# PocketPowerSource4_3.net
KiCad netlist of a schematic drawn in EAGLE
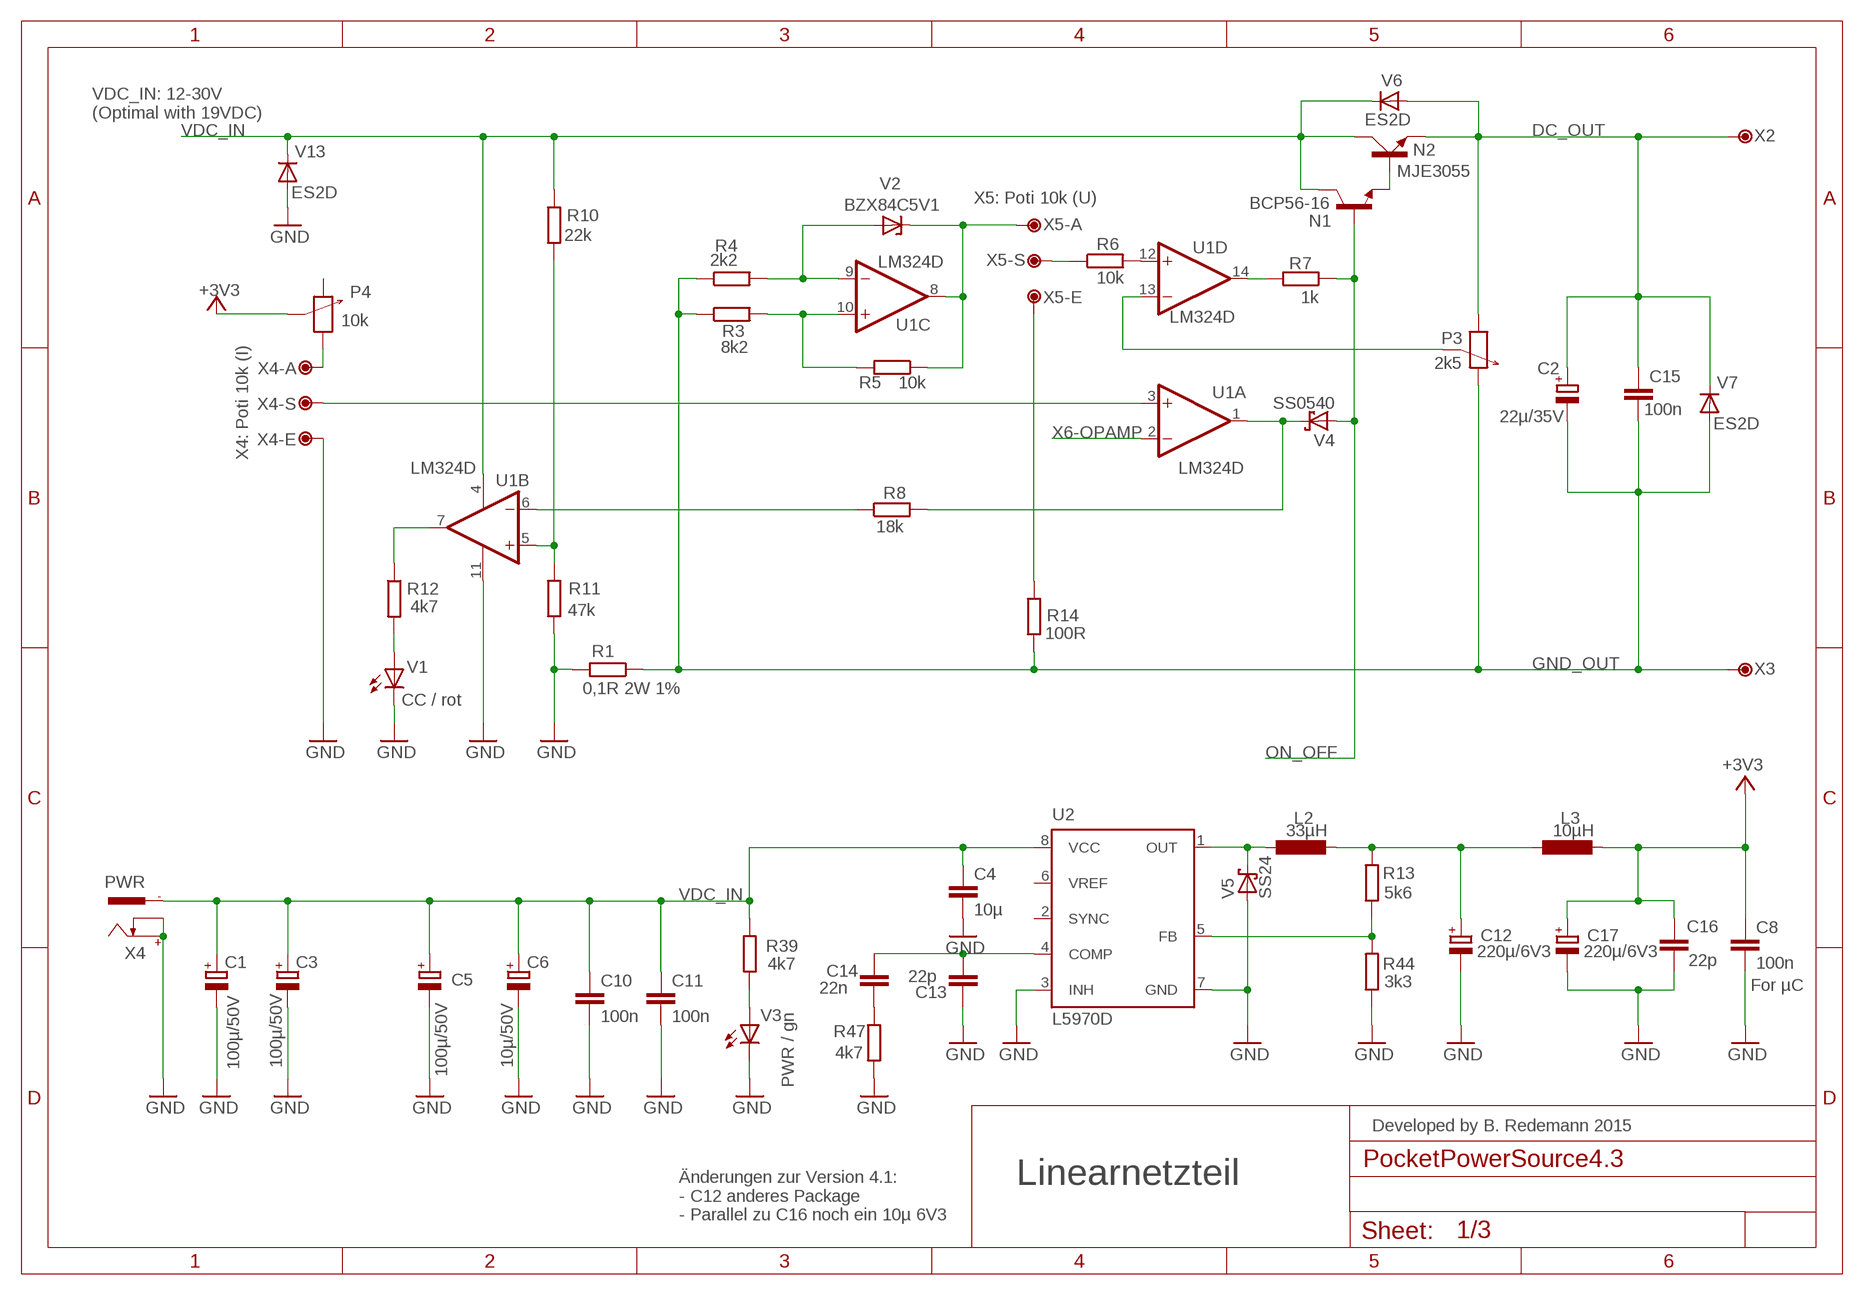
[diagram p0: schematic, sheet 1]
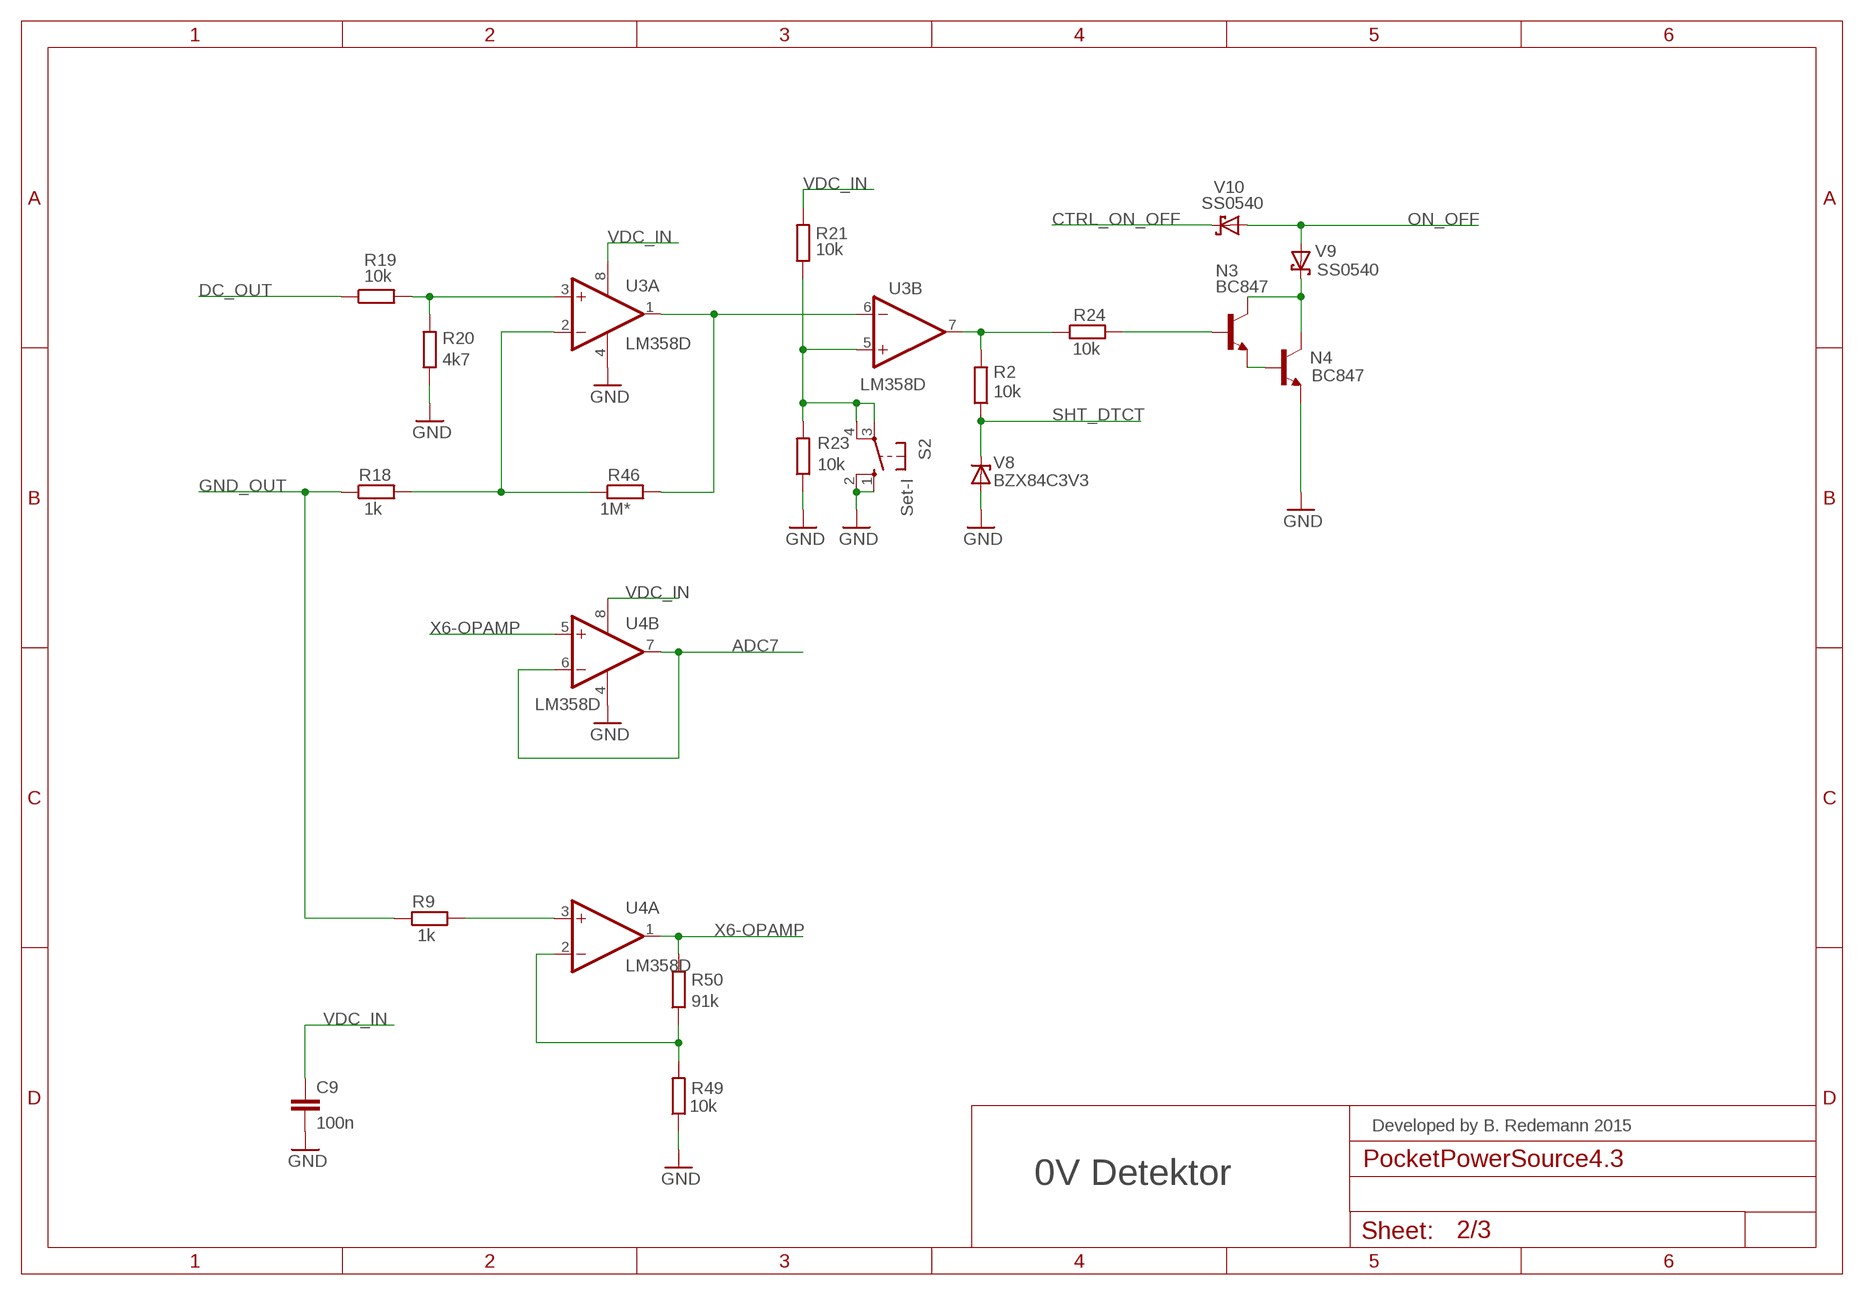
[diagram p1: schematic, sheet 2]
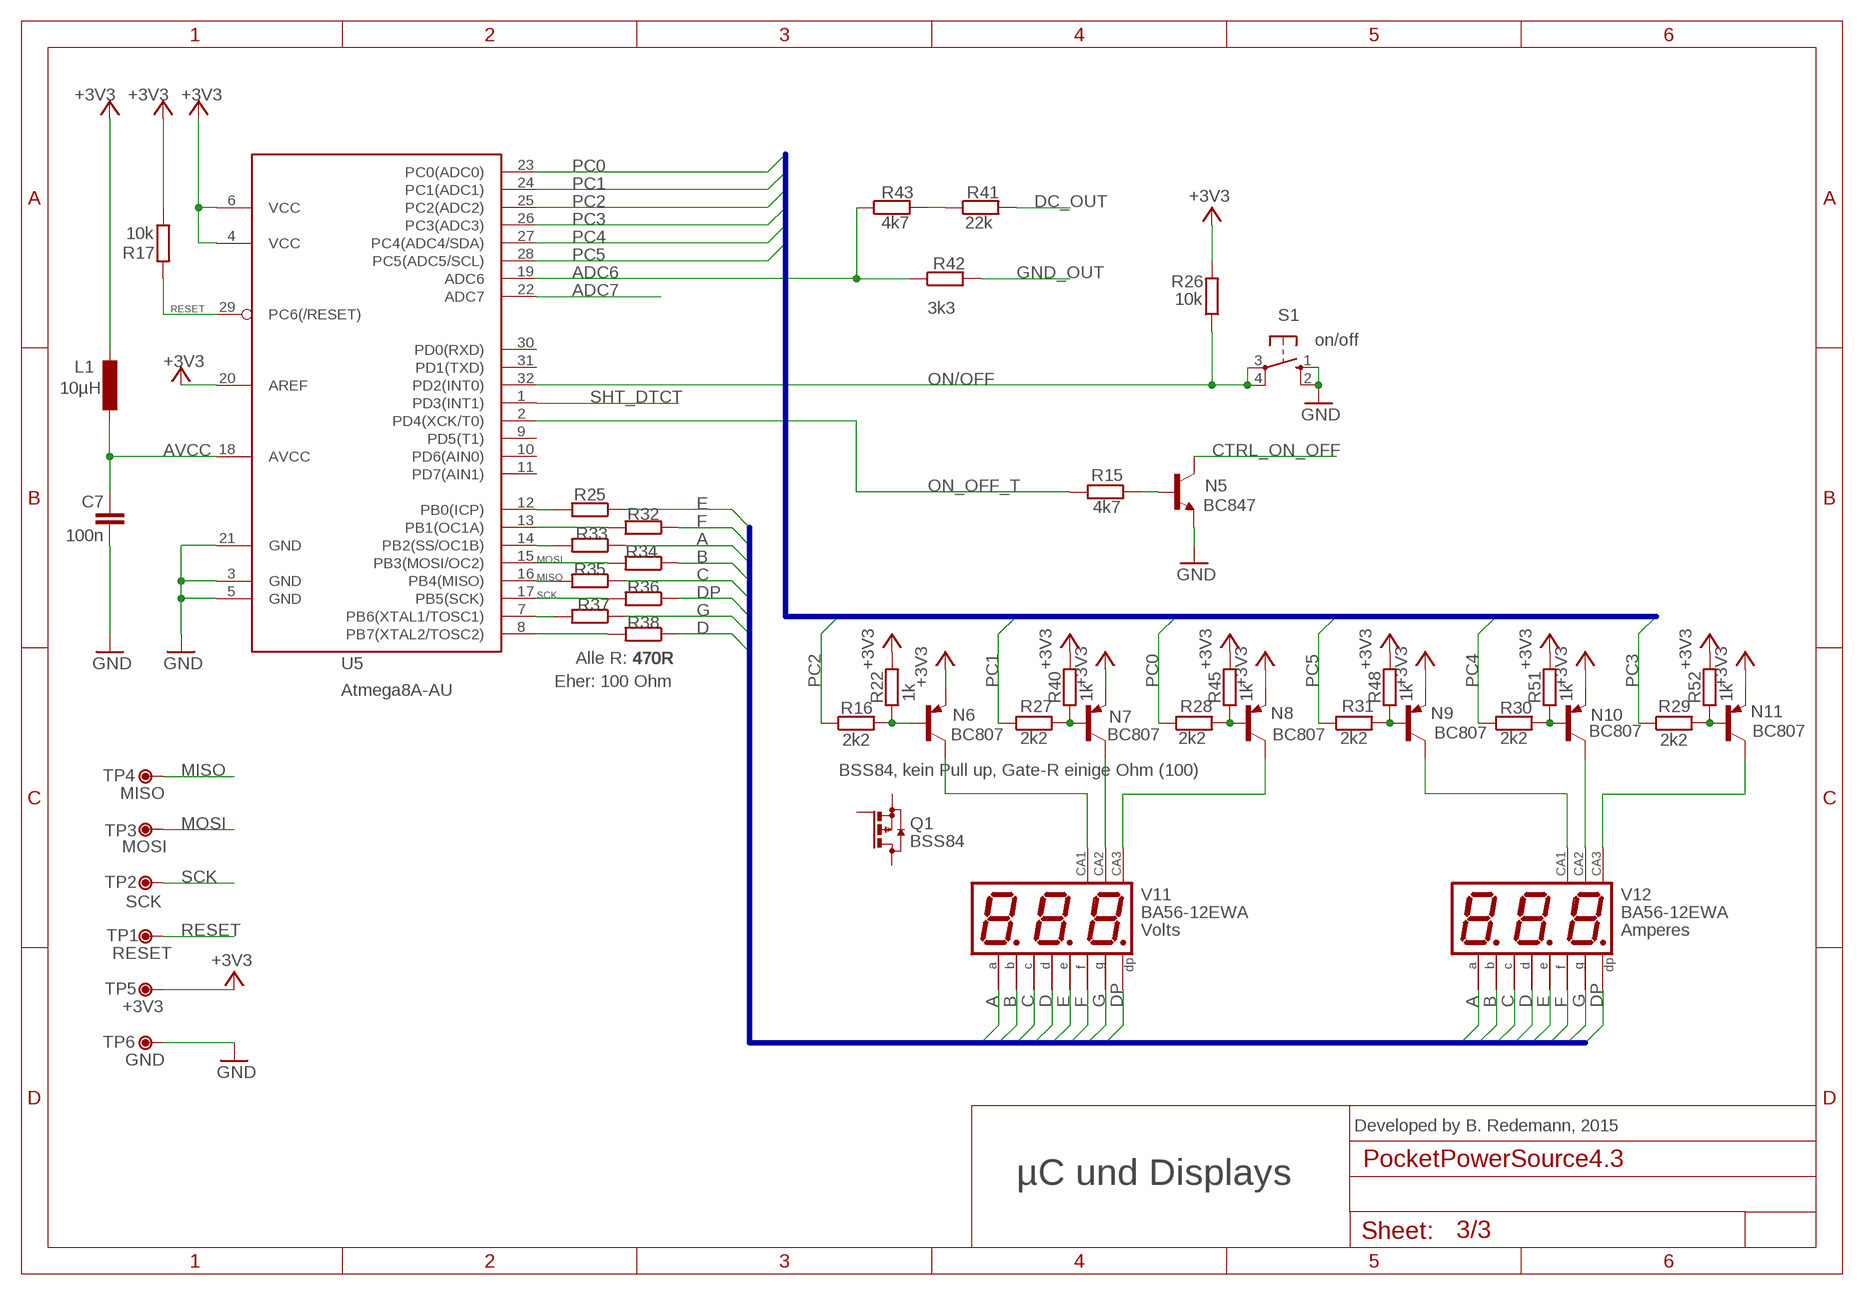
[diagram p2: schematic, sheet 3]

(export (version "E")
  (design (tool "Eeschema 10.0.6"))
  (components
    (comp (ref "C1")
      (value "100µ/50V")
      (footprint "eagle-import:PANASONIC_F")
      (libsource (lib "eagle-import") (part "CPOL-EUF"))
    )
    (comp (ref "C2")
      (value "22µ/35V")
      (footprint "eagle-import:PANASONIC_C")
      (libsource (lib "eagle-import") (part "CPOL-EUC"))
    )
    (comp (ref "C3")
      (value "100µ/50V")
      (footprint "eagle-import:PANASONIC_F")
      (libsource (lib "eagle-import") (part "CPOL-EUF"))
    )
    (comp (ref "C4")
      (value "10µ")
      (footprint "eagle-import:C1210")
      (libsource (lib "eagle-import") (part "C-EUC1210"))
    )
    (comp (ref "C5")
      (value "100µ/50V")
      (footprint "eagle-import:PANASONIC_F")
      (libsource (lib "eagle-import") (part "CPOL-EUF"))
    )
    (comp (ref "C6")
      (value "10µ/50V")
      (footprint "eagle-import:PANASONIC_D")
      (libsource (lib "eagle-import") (part "CPOL-EUD"))
    )
    (comp (ref "C8")
      (value "100n")
      (footprint "eagle-import:C0603K")
      (libsource (lib "eagle-import") (part "C-EUC0603K"))
    )
    (comp (ref "C10")
      (value "100n")
      (footprint "eagle-import:C0603K")
      (libsource (lib "eagle-import") (part "C-EUC0603K"))
    )
    (comp (ref "C11")
      (value "100n")
      (footprint "eagle-import:C0603K")
      (libsource (lib "eagle-import") (part "C-EUC0603K"))
    )
    (comp (ref "C12")
      (value "220µ/6V3")
      (footprint "eagle-import:PANASONIC_D")
      (libsource (lib "eagle-import") (part "CPOL-EUD"))
    )
    (comp (ref "C13")
      (value "22p")
      (footprint "eagle-import:C0805")
      (libsource (lib "eagle-import") (part "C-EUC0805"))
    )
    (comp (ref "C14")
      (value "22n")
      (footprint "eagle-import:C1206")
      (libsource (lib "eagle-import") (part "C-EUC1206"))
    )
    (comp (ref "C15")
      (value "100n")
      (footprint "eagle-import:C0603K")
      (libsource (lib "eagle-import") (part "C-EUC0603K"))
    )
    (comp (ref "C16")
      (value "22p")
      (footprint "eagle-import:C0805")
      (libsource (lib "eagle-import") (part "C-EUC0805"))
    )
    (comp (ref "C17")
      (value "220µ/6V3")
      (footprint "eagle-import:PANASONIC_D")
      (libsource (lib "eagle-import") (part "CPOL-EUD"))
    )
    (comp (ref "L2")
      (value "33µH")
      (footprint "eagle-import:POWER-CHOKE_WE-TPC")
      (libsource (lib "eagle-import") (part "L-EUWE-TPC"))
    )
    (comp (ref "L3")
      (value "10µH")
      (footprint "eagle-import:L4540")
      (libsource (lib "eagle-import") (part "L-EUL4540"))
    )
    (comp (ref "N1")
      (value "BCP56-16")
      (footprint "eagle-import:PG-SOT-223")
      (libsource (lib "eagle-import") (part "BCP56"))
    )
    (comp (ref "N2")
      (value "MJE3055")
      (footprint "eagle-import:TO220AV")
      (libsource (lib "eagle-import") (part "MJE3055"))
    )
    (comp (ref "P3")
      (value "2k5")
      (footprint "eagle-import:PT6")
      (libsource (lib "eagle-import") (part "PT6"))
    )
    (comp (ref "P4")
      (value "10k")
      (footprint "eagle-import:PT6")
      (libsource (lib "eagle-import") (part "PT6"))
    )
    (comp (ref "R1")
      (value "0,1R 2W 1%")
      (footprint "eagle-import:R2512")
      (libsource (lib "eagle-import") (part "R-EU_R2512"))
    )
    (comp (ref "R3")
      (value "8k2")
      (footprint "eagle-import:R0603")
      (libsource (lib "eagle-import") (part "R-EU_R0603"))
    )
    (comp (ref "R4")
      (value "2k2")
      (footprint "eagle-import:R0805")
      (libsource (lib "eagle-import") (part "R-EU_R0805"))
    )
    (comp (ref "R5")
      (value "10k")
      (footprint "eagle-import:R0603")
      (libsource (lib "eagle-import") (part "R-EU_R0603"))
    )
    (comp (ref "R6")
      (value "10k")
      (footprint "eagle-import:R0603")
      (libsource (lib "eagle-import") (part "R-EU_R0603"))
    )
    (comp (ref "R7")
      (value "1k")
      (footprint "eagle-import:R0603")
      (libsource (lib "eagle-import") (part "R-EU_R0603"))
    )
    (comp (ref "R8")
      (value "18k")
      (footprint "eagle-import:R1206")
      (libsource (lib "eagle-import") (part "R-EU_R1206"))
    )
    (comp (ref "R10")
      (value "22k")
      (footprint "eagle-import:R0603")
      (libsource (lib "eagle-import") (part "R-EU_R0603"))
    )
    (comp (ref "R11")
      (value "47k")
      (footprint "eagle-import:R0603")
      (libsource (lib "eagle-import") (part "R-EU_R0603"))
    )
    (comp (ref "R12")
      (value "4k7")
      (footprint "eagle-import:R1206")
      (libsource (lib "eagle-import") (part "R-EU_R1206"))
    )
    (comp (ref "R13")
      (value "5k6")
      (footprint "eagle-import:R0603")
      (libsource (lib "eagle-import") (part "R-EU_R0603"))
    )
    (comp (ref "R14")
      (value "100R")
      (footprint "eagle-import:R0603")
      (libsource (lib "eagle-import") (part "R-EU_R0603"))
    )
    (comp (ref "R39")
      (value "4k7")
      (footprint "eagle-import:R1206")
      (libsource (lib "eagle-import") (part "R-EU_R1206"))
    )
    (comp (ref "R44")
      (value "3k3")
      (footprint "eagle-import:R0603")
      (libsource (lib "eagle-import") (part "R-EU_R0603"))
    )
    (comp (ref "R47")
      (value "4k7")
      (footprint "eagle-import:R1206")
      (libsource (lib "eagle-import") (part "R-EU_R1206"))
    )
    (comp (ref "U1")
      (value "LM324D")
      (footprint "eagle-import:SO14")
      (fields (field (name "MF") "STMicroelectronics"))
      (libsource (lib "eagle-import") (part "LM324D"))
    )
    (comp (ref "U2")
      (value "L5970D")
      (footprint "eagle-import:SO08")
      (fields (field (name "MF") "STMicroelectronics"))
      (libsource (lib "eagle-import") (part "L5970D"))
    )
    (comp (ref "V1")
      (value "CC / rot")
      (footprint "eagle-import:LED3MM")
      (libsource (lib "eagle-import") (part "LED3MM"))
    )
    (comp (ref "V2")
      (value "BZX84C5V1")
      (footprint "eagle-import:TO236")
      (libsource (lib "eagle-import") (part "BZX84CSMD"))
    )
    (comp (ref "V3")
      (value "PWR / gn")
      (footprint "eagle-import:LED3MM")
      (libsource (lib "eagle-import") (part "LED3MM"))
    )
    (comp (ref "V4")
      (value "SS0540")
      (footprint "eagle-import:SOD123")
      (libsource (lib "eagle-import") (part "SS0540"))
    )
    (comp (ref "V5")
      (value "SS24")
      (footprint "eagle-import:SMB")
      (libsource (lib "eagle-import") (part "MBRS130LT3"))
    )
    (comp (ref "V6")
      (value "ES2D")
      (footprint "eagle-import:SMB")
      (libsource (lib "eagle-import") (part "ES2D"))
    )
    (comp (ref "V7")
      (value "ES2D")
      (footprint "eagle-import:SMB")
      (libsource (lib "eagle-import") (part "ES2D"))
    )
    (comp (ref "V13")
      (value "ES2D")
      (footprint "eagle-import:SMB")
      (libsource (lib "eagle-import") (part "ES2D"))
    )
    (comp (ref "X2")
      (value "DC_OUT")
      (footprint "eagle-import:P1-13")
      (libsource (lib "eagle-import") (part "TPPAD1-13"))
    )
    (comp (ref "X3")
      (value "GND_OUT")
      (footprint "eagle-import:P1-13")
      (libsource (lib "eagle-import") (part "TPPAD1-13"))
    )
    (comp (ref "X4")
      (value "PWR")
      (footprint "eagle-import:737992-5")
      (libsource (lib "eagle-import") (part "737992-55"))
    )
    (comp (ref "X4-A")
      (value "P_I-A")
      (footprint "eagle-import:P1-13")
      (libsource (lib "eagle-import") (part "TPPAD1-13"))
    )
    (comp (ref "X4-E")
      (value "P_I-E")
      (footprint "eagle-import:P1-13")
      (libsource (lib "eagle-import") (part "TPPAD1-13"))
    )
    (comp (ref "X4-S")
      (value "P_I-W")
      (footprint "eagle-import:P1-13")
      (libsource (lib "eagle-import") (part "TPPAD1-13"))
    )
    (comp (ref "X5-A")
      (value "P_U-A")
      (footprint "eagle-import:P1-13")
      (libsource (lib "eagle-import") (part "TPPAD1-13"))
    )
    (comp (ref "X5-E")
      (value "P_U-E")
      (footprint "eagle-import:P1-13")
      (libsource (lib "eagle-import") (part "TPPAD1-13"))
    )
    (comp (ref "X5-S")
      (value "P_U-S")
      (footprint "eagle-import:P1-13")
      (libsource (lib "eagle-import") (part "TPPAD1-13"))
    )
    (comp (ref "C9")
      (value "100n")
      (footprint "eagle-import:C0603K")
      (libsource (lib "eagle-import") (part "C-EUC0603K"))
    )
    (comp (ref "N3")
      (value "BC847")
      (footprint "eagle-import:SOT23")
      (libsource (lib "eagle-import") (part "BC847"))
    )
    (comp (ref "N4")
      (value "BC847")
      (footprint "eagle-import:SOT23")
      (libsource (lib "eagle-import") (part "BC847"))
    )
    (comp (ref "R2")
      (value "10k")
      (footprint "eagle-import:R0603")
      (libsource (lib "eagle-import") (part "R-EU_R0603"))
    )
    (comp (ref "R9")
      (value "1k")
      (footprint "eagle-import:R0603")
      (libsource (lib "eagle-import") (part "R-EU_R0603"))
    )
    (comp (ref "R18")
      (value "1k")
      (footprint "eagle-import:R0603")
      (libsource (lib "eagle-import") (part "R-EU_R0603"))
    )
    (comp (ref "R19")
      (value "10k")
      (footprint "eagle-import:R0603")
      (libsource (lib "eagle-import") (part "R-EU_R0603"))
    )
    (comp (ref "R20")
      (value "4k7")
      (footprint "eagle-import:R1206")
      (libsource (lib "eagle-import") (part "R-EU_R1206"))
    )
    (comp (ref "R21")
      (value "10k")
      (footprint "eagle-import:R0603")
      (libsource (lib "eagle-import") (part "R-EU_R0603"))
    )
    (comp (ref "R23")
      (value "10k")
      (footprint "eagle-import:R0603")
      (libsource (lib "eagle-import") (part "R-EU_R0603"))
    )
    (comp (ref "R24")
      (value "10k")
      (footprint "eagle-import:R0603")
      (libsource (lib "eagle-import") (part "R-EU_R0603"))
    )
    (comp (ref "R46")
      (value "1M*")
      (footprint "eagle-import:R0603")
      (libsource (lib "eagle-import") (part "R-EU_R0603"))
    )
    (comp (ref "R49")
      (value "10k")
      (footprint "eagle-import:R0603")
      (libsource (lib "eagle-import") (part "R-EU_R0603"))
    )
    (comp (ref "R50")
      (value "91k")
      (footprint "eagle-import:R0805")
      (libsource (lib "eagle-import") (part "R-EU_R0805"))
    )
    (comp (ref "S2")
      (value "Set-I")
      (footprint "eagle-import:B3F-10XX")
      (fields (field (name "MPN") "B3F-1000"))
      (libsource (lib "eagle-import") (part "10-XX"))
    )
    (comp (ref "U3")
      (value "LM358D")
      (footprint "eagle-import:SO08")
      (fields (field (name "MF") "STMicroelectronics"))
      (libsource (lib "eagle-import") (part "LM358D"))
    )
    (comp (ref "U4")
      (value "LM358D")
      (footprint "eagle-import:SO08")
      (fields (field (name "MF") "STMicroelectronics"))
      (libsource (lib "eagle-import") (part "LM358D"))
    )
    (comp (ref "V8")
      (value "BZX84C3V3")
      (footprint "eagle-import:TO236")
      (libsource (lib "eagle-import") (part "BZX84CSMD"))
    )
    (comp (ref "V9")
      (value "SS0540")
      (footprint "eagle-import:SOD123")
      (libsource (lib "eagle-import") (part "SS0540"))
    )
    (comp (ref "V10")
      (value "SS0540")
      (footprint "eagle-import:SOD123")
      (libsource (lib "eagle-import") (part "SS0540"))
    )
    (comp (ref "C7")
      (value "100n")
      (footprint "eagle-import:C0603K")
      (libsource (lib "eagle-import") (part "C-EUC0603K"))
    )
    (comp (ref "L1")
      (value "10µH")
      (footprint "eagle-import:L2825P")
      (libsource (lib "eagle-import") (part "resistor_L-EUL2825P"))
    )
    (comp (ref "N5")
      (value "BC847")
      (footprint "eagle-import:SOT23")
      (libsource (lib "eagle-import") (part "BC847"))
    )
    (comp (ref "N6")
      (value "BC807")
      (footprint "eagle-import:SOT23-BEC")
      (libsource (lib "eagle-import") (part "-PNP-SOT23-BECBC807-16"))
    )
    (comp (ref "N7")
      (value "BC807")
      (footprint "eagle-import:SOT23-BEC")
      (libsource (lib "eagle-import") (part "-PNP-SOT23-BECBC807-16"))
    )
    (comp (ref "N8")
      (value "BC807")
      (footprint "eagle-import:SOT23-BEC")
      (libsource (lib "eagle-import") (part "-PNP-SOT23-BECBC807-16"))
    )
    (comp (ref "N9")
      (value "BC807")
      (footprint "eagle-import:SOT23-BEC")
      (libsource (lib "eagle-import") (part "-PNP-SOT23-BECBC807-16"))
    )
    (comp (ref "N10")
      (value "BC807")
      (footprint "eagle-import:SOT23-BEC")
      (libsource (lib "eagle-import") (part "-PNP-SOT23-BECBC807-16"))
    )
    (comp (ref "N11")
      (value "BC807")
      (footprint "eagle-import:SOT23-BEC")
      (libsource (lib "eagle-import") (part "-PNP-SOT23-BECBC807-16"))
    )
    (comp (ref "Q1")
      (value "BSS84")
      (footprint "eagle-import:SOT23")
      (libsource (lib "eagle-import") (part "BSS84"))
    )
    (comp (ref "R15")
      (value "4k7")
      (footprint "eagle-import:R1206")
      (libsource (lib "eagle-import") (part "R-EU_R1206"))
    )
    (comp (ref "R16")
      (value "2k2")
      (footprint "eagle-import:R1206")
      (libsource (lib "eagle-import") (part "R-EU_R1206"))
    )
    (comp (ref "R17")
      (value "10k")
      (footprint "eagle-import:R0603")
      (libsource (lib "eagle-import") (part "R-EU_R0603"))
    )
    (comp (ref "R22")
      (value "1k")
      (footprint "eagle-import:R0603")
      (libsource (lib "eagle-import") (part "R-EU_R0603"))
    )
    (comp (ref "R25")
      (value "470R")
      (footprint "eagle-import:R0805")
      (libsource (lib "eagle-import") (part "R-EU_R0805"))
    )
    (comp (ref "R26")
      (value "10k")
      (footprint "eagle-import:R0603")
      (libsource (lib "eagle-import") (part "R-EU_R0603"))
    )
    (comp (ref "R27")
      (value "2k2")
      (footprint "eagle-import:R1206")
      (libsource (lib "eagle-import") (part "R-EU_R1206"))
    )
    (comp (ref "R28")
      (value "2k2")
      (footprint "eagle-import:R1206")
      (libsource (lib "eagle-import") (part "R-EU_R1206"))
    )
    (comp (ref "R29")
      (value "2k2")
      (footprint "eagle-import:R1206")
      (libsource (lib "eagle-import") (part "R-EU_R1206"))
    )
    (comp (ref "R30")
      (value "2k2")
      (footprint "eagle-import:R1206")
      (libsource (lib "eagle-import") (part "R-EU_R1206"))
    )
    (comp (ref "R31")
      (value "2k2")
      (footprint "eagle-import:R1206")
      (libsource (lib "eagle-import") (part "R-EU_R1206"))
    )
    (comp (ref "R32")
      (value "470R")
      (footprint "eagle-import:R0805")
      (libsource (lib "eagle-import") (part "R-EU_R0805"))
    )
    (comp (ref "R33")
      (value "470R")
      (footprint "eagle-import:R0805")
      (libsource (lib "eagle-import") (part "R-EU_R0805"))
    )
    (comp (ref "R34")
      (value "470R")
      (footprint "eagle-import:R0805")
      (libsource (lib "eagle-import") (part "R-EU_R0805"))
    )
    (comp (ref "R35")
      (value "470R")
      (footprint "eagle-import:R0805")
      (libsource (lib "eagle-import") (part "R-EU_R0805"))
    )
    (comp (ref "R36")
      (value "470R")
      (footprint "eagle-import:R0805")
      (libsource (lib "eagle-import") (part "R-EU_R0805"))
    )
    (comp (ref "R37")
      (value "470R")
      (footprint "eagle-import:R0805")
      (libsource (lib "eagle-import") (part "R-EU_R0805"))
    )
    (comp (ref "R38")
      (value "470R")
      (footprint "eagle-import:R0805")
      (libsource (lib "eagle-import") (part "R-EU_R0805"))
    )
    (comp (ref "R40")
      (value "1k")
      (footprint "eagle-import:R0603")
      (libsource (lib "eagle-import") (part "R-EU_R0603"))
    )
    (comp (ref "R41")
      (value "22k")
      (footprint "eagle-import:R0603")
      (libsource (lib "eagle-import") (part "R-EU_R0603"))
    )
    (comp (ref "R42")
      (value "3k3")
      (footprint "eagle-import:R0603")
      (libsource (lib "eagle-import") (part "R-EU_R0603"))
    )
    (comp (ref "R43")
      (value "4k7")
      (footprint "eagle-import:R1206")
      (libsource (lib "eagle-import") (part "R-EU_R1206"))
    )
    (comp (ref "R45")
      (value "1k")
      (footprint "eagle-import:R0603")
      (libsource (lib "eagle-import") (part "R-EU_R0603"))
    )
    (comp (ref "R48")
      (value "1k")
      (footprint "eagle-import:R0603")
      (libsource (lib "eagle-import") (part "R-EU_R0603"))
    )
    (comp (ref "R51")
      (value "1k")
      (footprint "eagle-import:R0603")
      (libsource (lib "eagle-import") (part "R-EU_R0603"))
    )
    (comp (ref "R52")
      (value "1k")
      (footprint "eagle-import:R0603")
      (libsource (lib "eagle-import") (part "R-EU_R0603"))
    )
    (comp (ref "S1")
      (value "on/off")
      (footprint "eagle-import:B3F-10XX")
      (fields (field (name "MPN") "B3F-1000"))
      (libsource (lib "eagle-import") (part "10-XX"))
    )
    (comp (ref "TP1")
      (value "RESET")
      (footprint "eagle-import:P1-13")
      (libsource (lib "eagle-import") (part "TPPAD1-13"))
    )
    (comp (ref "TP2")
      (value "SCK")
      (footprint "eagle-import:P1-13")
      (libsource (lib "eagle-import") (part "TPPAD1-13"))
    )
    (comp (ref "TP3")
      (value "MOSI")
      (footprint "eagle-import:P1-13")
      (libsource (lib "eagle-import") (part "TPPAD1-13"))
    )
    (comp (ref "TP4")
      (value "MISO")
      (footprint "eagle-import:P1-13")
      (libsource (lib "eagle-import") (part "TPPAD1-13"))
    )
    (comp (ref "TP5")
      (value "+3V3")
      (footprint "eagle-import:P1-13")
      (libsource (lib "eagle-import") (part "TPPAD1-13"))
    )
    (comp (ref "TP6")
      (value "GND")
      (footprint "eagle-import:P1-13")
      (libsource (lib "eagle-import") (part "TPPAD1-13"))
    )
    (comp (ref "U5")
      (value "Atmega8A-AU")
      (footprint "eagle-import:TQFP32-08")
      (fields (field (name "MPN") "ATMEGA8-16AU"))
      (libsource (lib "eagle-import") (part "MEGA8-AI"))
    )
    (comp (ref "V11")
      (value "BA56-12EWA")
      (footprint "eagle-import:BX56-12")
      (libsource (lib "eagle-import") (part "B?56-12WAAE"))
    )
    (comp (ref "V12")
      (value "BA56-12EWA")
      (footprint "eagle-import:BX56-12")
      (libsource (lib "eagle-import") (part "B?56-12WAAE"))
    )
  )
  (nets
    (net (code "1") (name "+3V3") (class "Default")
      (node (ref "C16") (pin "2") (pinfunction "2_2") (pintype "passive"))
      (node (ref "C17") (pin "+") (pinfunction "+_+") (pintype "passive"))
      (node (ref "C8") (pin "1") (pinfunction "1_1") (pintype "passive"))
      (node (ref "L1") (pin "1") (pinfunction "1_1") (pintype "passive"))
      (node (ref "L3") (pin "P$2") (pinfunction "2_P$2") (pintype "passive"))
      (node (ref "N10") (pin "E") (pinfunction "E_E") (pintype "passive"))
      (node (ref "N11") (pin "E") (pinfunction "E_E") (pintype "passive"))
      (node (ref "N6") (pin "E") (pinfunction "E_E") (pintype "passive"))
      (node (ref "N7") (pin "E") (pinfunction "E_E") (pintype "passive"))
      (node (ref "N8") (pin "E") (pinfunction "E_E") (pintype "passive"))
      (node (ref "N9") (pin "E") (pinfunction "E_E") (pintype "passive"))
      (node (ref "P4") (pin "WIPER") (pinfunction "1S_WIPER") (pintype "passive"))
      (node (ref "R17") (pin "1") (pinfunction "1_1") (pintype "passive"))
      (node (ref "R22") (pin "2") (pinfunction "2_2") (pintype "passive"))
      (node (ref "R26") (pin "2") (pinfunction "2_2") (pintype "passive"))
      (node (ref "R40") (pin "2") (pinfunction "2_2") (pintype "passive"))
      (node (ref "R45") (pin "2") (pinfunction "2_2") (pintype "passive"))
      (node (ref "R48") (pin "2") (pinfunction "2_2") (pintype "passive"))
      (node (ref "R51") (pin "2") (pinfunction "2_2") (pintype "passive"))
      (node (ref "R52") (pin "2") (pinfunction "2_2") (pintype "passive"))
      (node (ref "TP5") (pin "TP") (pinfunction "TP_TP") (pintype "bidirectional"))
      (node (ref "U5") (pin "20") (pinfunction "AREF_20") (pintype "passive"))
      (node (ref "U5") (pin "4") (pinfunction "VCC_4") (pintype "power_in"))
      (node (ref "U5") (pin "6") (pinfunction "VCC_6") (pintype "power_in"))
    )
    (net (code "2") (name "A") (class "Default")
      (node (ref "R33") (pin "1") (pinfunction "1_1") (pintype "passive"))
      (node (ref "V11") (pin "11") (pinfunction "A_11") (pintype "passive"))
      (node (ref "V12") (pin "11") (pinfunction "A_11") (pintype "passive"))
    )
    (net (code "3") (name "ADC6") (class "Default")
      (node (ref "R42") (pin "1") (pinfunction "1_1") (pintype "passive"))
      (node (ref "R43") (pin "1") (pinfunction "1_1") (pintype "passive"))
      (node (ref "U5") (pin "19") (pinfunction "ADC6_19") (pintype "bidirectional"))
    )
    (net (code "4") (name "ADC7") (class "Default")
      (node (ref "U4") (pin "6") (pinfunction "-IN_6") (pintype "input"))
      (node (ref "U4") (pin "7") (pinfunction "OUT_7") (pintype "output"))
      (node (ref "U5") (pin "22") (pinfunction "ADC7_22") (pintype "bidirectional"))
    )
    (net (code "5") (name "AVCC") (class "Default")
      (node (ref "C7") (pin "1") (pinfunction "1_1") (pintype "passive"))
      (node (ref "L1") (pin "2") (pinfunction "2_2") (pintype "passive"))
      (node (ref "U5") (pin "18") (pinfunction "AVCC_18") (pintype "power_in"))
    )
    (net (code "6") (name "B") (class "Default")
      (node (ref "R34") (pin "1") (pinfunction "1_1") (pintype "passive"))
      (node (ref "V11") (pin "7") (pinfunction "B_7") (pintype "passive"))
      (node (ref "V12") (pin "7") (pinfunction "B_7") (pintype "passive"))
    )
    (net (code "7") (name "C") (class "Default")
      (node (ref "R35") (pin "1") (pinfunction "1_1") (pintype "passive"))
      (node (ref "V11") (pin "4") (pinfunction "C_4") (pintype "passive"))
      (node (ref "V12") (pin "4") (pinfunction "C_4") (pintype "passive"))
    )
    (net (code "8") (name "CTRL_ON_OFF") (class "Default")
      (node (ref "N5") (pin "3") (pinfunction "C_3") (pintype "passive"))
      (node (ref "V10") (pin "C") (pinfunction "C_C") (pintype "passive"))
    )
    (net (code "9") (name "D") (class "Default")
      (node (ref "R38") (pin "1") (pinfunction "1_1") (pintype "passive"))
      (node (ref "V11") (pin "2") (pinfunction "D_2") (pintype "passive"))
      (node (ref "V12") (pin "2") (pinfunction "D_2") (pintype "passive"))
    )
    (net (code "10") (name "DC_OUT") (class "Default")
      (node (ref "C15") (pin "1") (pinfunction "1_1") (pintype "passive"))
      (node (ref "C2") (pin "+") (pinfunction "+_+") (pintype "passive"))
      (node (ref "N2") (pin "E") (pinfunction "E_E") (pintype "passive"))
      (node (ref "P3") (pin "RIGHT") (pinfunction "1E_RIGHT") (pintype "passive"))
      (node (ref "R19") (pin "1") (pinfunction "1_1") (pintype "passive"))
      (node (ref "R41") (pin "2") (pinfunction "2_2") (pintype "passive"))
      (node (ref "V6") (pin "A") (pinfunction "A_A") (pintype "passive"))
      (node (ref "V7") (pin "C") (pinfunction "C_C") (pintype "passive"))
      (node (ref "X2") (pin "TP") (pinfunction "TP_TP") (pintype "bidirectional"))
    )
    (net (code "11") (name "DP") (class "Default")
      (node (ref "R36") (pin "1") (pinfunction "1_1") (pintype "passive"))
      (node (ref "V11") (pin "3") (pinfunction "DP_3") (pintype "passive"))
      (node (ref "V12") (pin "3") (pinfunction "DP_3") (pintype "passive"))
    )
    (net (code "12") (name "E") (class "Default")
      (node (ref "R25") (pin "1") (pinfunction "1_1") (pintype "passive"))
      (node (ref "V11") (pin "1") (pinfunction "E_1") (pintype "passive"))
      (node (ref "V12") (pin "1") (pinfunction "E_1") (pintype "passive"))
    )
    (net (code "13") (name "F") (class "Default")
      (node (ref "R32") (pin "1") (pinfunction "1_1") (pintype "passive"))
      (node (ref "V11") (pin "10") (pinfunction "F_10") (pintype "passive"))
      (node (ref "V12") (pin "10") (pinfunction "F_10") (pintype "passive"))
    )
    (net (code "14") (name "G") (class "Default")
      (node (ref "R37") (pin "1") (pinfunction "1_1") (pintype "passive"))
      (node (ref "V11") (pin "5") (pinfunction "G_5") (pintype "passive"))
      (node (ref "V12") (pin "5") (pinfunction "G_5") (pintype "passive"))
    )
    (net (code "15") (name "GND") (class "Default")
      (node (ref "C1") (pin "-") (pinfunction "-_-") (pintype "passive"))
      (node (ref "C10") (pin "2") (pinfunction "2_2") (pintype "passive"))
      (node (ref "C11") (pin "2") (pinfunction "2_2") (pintype "passive"))
      (node (ref "C12") (pin "-") (pinfunction "-_-") (pintype "passive"))
      (node (ref "C13") (pin "1") (pinfunction "1_1") (pintype "passive"))
      (node (ref "C16") (pin "1") (pinfunction "1_1") (pintype "passive"))
      (node (ref "C17") (pin "-") (pinfunction "-_-") (pintype "passive"))
      (node (ref "C3") (pin "-") (pinfunction "-_-") (pintype "passive"))
      (node (ref "C4") (pin "2") (pinfunction "2_2") (pintype "passive"))
      (node (ref "C5") (pin "-") (pinfunction "-_-") (pintype "passive"))
      (node (ref "C6") (pin "-") (pinfunction "-_-") (pintype "passive"))
      (node (ref "C7") (pin "2") (pinfunction "2_2") (pintype "passive"))
      (node (ref "C8") (pin "2") (pinfunction "2_2") (pintype "passive"))
      (node (ref "C9") (pin "2") (pinfunction "2_2") (pintype "passive"))
      (node (ref "N4") (pin "2") (pinfunction "E_2") (pintype "passive"))
      (node (ref "N5") (pin "2") (pinfunction "E_2") (pintype "passive"))
      (node (ref "R1") (pin "2") (pinfunction "2_2") (pintype "passive"))
      (node (ref "R11") (pin "1") (pinfunction "1_1") (pintype "passive"))
      (node (ref "R20") (pin "1") (pinfunction "1_1") (pintype "passive"))
      (node (ref "R23") (pin "1") (pinfunction "1_1") (pintype "passive"))
      (node (ref "R44") (pin "1") (pinfunction "1_1") (pintype "passive"))
      (node (ref "R47") (pin "1") (pinfunction "1_1") (pintype "passive"))
      (node (ref "R49") (pin "1") (pinfunction "1_1") (pintype "passive"))
      (node (ref "S1") (pin "1") (pinfunction "S_1") (pintype "passive"))
      (node (ref "S1") (pin "2") (pinfunction "S1_2") (pintype "passive"))
      (node (ref "S2") (pin "1") (pinfunction "S_1") (pintype "passive"))
      (node (ref "S2") (pin "2") (pinfunction "S1_2") (pintype "passive"))
      (node (ref "TP6") (pin "TP") (pinfunction "TP_TP") (pintype "bidirectional"))
      (node (ref "U1") (pin "11") (pinfunction "V-_11") (pintype "power_in"))
      (node (ref "U2") (pin "3") (pinfunction "INH_3") (pintype "input"))
      (node (ref "U2") (pin "7") (pinfunction "GND_7") (pintype "power_in"))
      (node (ref "U3") (pin "4") (pinfunction "V-_4") (pintype "power_in"))
      (node (ref "U4") (pin "4") (pinfunction "V-_4") (pintype "power_in"))
      (node (ref "U5") (pin "21") (pinfunction "GND_21") (pintype "power_in"))
      (node (ref "U5") (pin "3") (pinfunction "GND_3") (pintype "power_in"))
      (node (ref "U5") (pin "5") (pinfunction "GND_5") (pintype "power_in"))
      (node (ref "V1") (pin "K") (pinfunction "C_K") (pintype "passive"))
      (node (ref "V13") (pin "A") (pinfunction "A_A") (pintype "passive"))
      (node (ref "V3") (pin "K") (pinfunction "C_K") (pintype "passive"))
      (node (ref "V5") (pin "A") (pinfunction "A_A") (pintype "passive"))
      (node (ref "V8") (pin "A") (pinfunction "A_A") (pintype "passive"))
      (node (ref "X4") (pin "+") (pinfunction "+_+") (pintype "passive"))
      (node (ref "X4") (pin "K") (pinfunction "K_K") (pintype "passive"))
      (node (ref "X4-E") (pin "TP") (pinfunction "TP_TP") (pintype "bidirectional"))
    )
    (net (code "16") (name "GND_OUT") (class "Default")
      (node (ref "C15") (pin "2") (pinfunction "2_2") (pintype "passive"))
      (node (ref "C2") (pin "-") (pinfunction "-_-") (pintype "passive"))
      (node (ref "P3") (pin "LEFT") (pinfunction "1A_LEFT") (pintype "passive"))
      (node (ref "R1") (pin "1") (pinfunction "1_1") (pintype "passive"))
      (node (ref "R14") (pin "2") (pinfunction "2_2") (pintype "passive"))
      (node (ref "R18") (pin "1") (pinfunction "1_1") (pintype "passive"))
      (node (ref "R3") (pin "1") (pinfunction "1_1") (pintype "passive"))
      (node (ref "R4") (pin "1") (pinfunction "1_1") (pintype "passive"))
      (node (ref "R42") (pin "2") (pinfunction "2_2") (pintype "passive"))
      (node (ref "R9") (pin "1") (pinfunction "1_1") (pintype "passive"))
      (node (ref "V7") (pin "A") (pinfunction "A_A") (pintype "passive"))
      (node (ref "X3") (pin "TP") (pinfunction "TP_TP") (pintype "bidirectional"))
    )
    (net (code "17") (name "MISO") (class "Default")
      (node (ref "R35") (pin "2") (pinfunction "2_2") (pintype "passive"))
      (node (ref "TP4") (pin "TP") (pinfunction "TP_TP") (pintype "bidirectional"))
      (node (ref "U5") (pin "16") (pinfunction "PB4(MISO)_16") (pintype "bidirectional"))
    )
    (net (code "18") (name "MOSI") (class "Default")
      (node (ref "R34") (pin "2") (pinfunction "2_2") (pintype "passive"))
      (node (ref "TP3") (pin "TP") (pinfunction "TP_TP") (pintype "bidirectional"))
      (node (ref "U5") (pin "15") (pinfunction "PB3(MOSI/OC2)_15") (pintype "bidirectional"))
    )
    (net (code "19") (name "Net-(C14-Pad2)") (class "Default")
      (node (ref "C14") (pin "2") (pinfunction "2_2") (pintype "passive"))
      (node (ref "R47") (pin "2") (pinfunction "2_2") (pintype "passive"))
    )
    (net (code "20") (name "Net-(L3-1)") (class "Default")
      (node (ref "C12") (pin "+") (pinfunction "+_+") (pintype "passive"))
      (node (ref "L2") (pin "2") (pinfunction "2_2") (pintype "passive"))
      (node (ref "L3") (pin "P$1") (pinfunction "1_P$1") (pintype "passive"))
      (node (ref "R13") (pin "2") (pinfunction "2_2") (pintype "passive"))
    )
    (net (code "21") (name "Net-(N1-E)") (class "Default")
      (node (ref "N1") (pin "3") (pinfunction "E_3") (pintype "passive"))
      (node (ref "N2") (pin "B") (pinfunction "B_B") (pintype "passive"))
    )
    (net (code "22") (name "Net-(N3-B)") (class "Default")
      (node (ref "N3") (pin "1") (pinfunction "B_1") (pintype "passive"))
      (node (ref "R24") (pin "2") (pinfunction "2_2") (pintype "passive"))
    )
    (net (code "23") (name "Net-(N3-C)") (class "Default")
      (node (ref "N3") (pin "3") (pinfunction "C_3") (pintype "passive"))
      (node (ref "N4") (pin "3") (pinfunction "C_3") (pintype "passive"))
      (node (ref "V9") (pin "C") (pinfunction "C_C") (pintype "passive"))
    )
    (net (code "24") (name "Net-(N3-E)") (class "Default")
      (node (ref "N3") (pin "2") (pinfunction "E_2") (pintype "passive"))
      (node (ref "N4") (pin "1") (pinfunction "B_1") (pintype "passive"))
    )
    (net (code "25") (name "Net-(N5-B)") (class "Default")
      (node (ref "N5") (pin "1") (pinfunction "B_1") (pintype "passive"))
      (node (ref "R15") (pin "1") (pinfunction "1_1") (pintype "passive"))
    )
    (net (code "26") (name "Net-(N6-PadB)") (class "Default")
      (node (ref "N6") (pin "B") (pinfunction "B_B") (pintype "passive"))
      (node (ref "R16") (pin "2") (pinfunction "2_2") (pintype "passive"))
      (node (ref "R22") (pin "1") (pinfunction "1_1") (pintype "passive"))
    )
    (net (code "27") (name "Net-(N6-PadC)") (class "Default")
      (node (ref "N6") (pin "C") (pinfunction "C_C") (pintype "passive"))
      (node (ref "V11") (pin "12") (pinfunction "CA_12") (pintype "passive"))
    )
    (net (code "28") (name "Net-(N7-PadB)") (class "Default")
      (node (ref "N7") (pin "B") (pinfunction "B_B") (pintype "passive"))
      (node (ref "R27") (pin "2") (pinfunction "2_2") (pintype "passive"))
      (node (ref "R40") (pin "1") (pinfunction "1_1") (pintype "passive"))
    )
    (net (code "29") (name "Net-(N7-PadC)") (class "Default")
      (node (ref "N7") (pin "C") (pinfunction "C_C") (pintype "passive"))
      (node (ref "V11") (pin "9") (pinfunction "CA_9") (pintype "passive"))
    )
    (net (code "30") (name "Net-(N8-PadB)") (class "Default")
      (node (ref "N8") (pin "B") (pinfunction "B_B") (pintype "passive"))
      (node (ref "R28") (pin "2") (pinfunction "2_2") (pintype "passive"))
      (node (ref "R45") (pin "1") (pinfunction "1_1") (pintype "passive"))
    )
    (net (code "31") (name "Net-(N8-PadC)") (class "Default")
      (node (ref "N8") (pin "C") (pinfunction "C_C") (pintype "passive"))
      (node (ref "V11") (pin "8") (pinfunction "CA_8") (pintype "passive"))
    )
    (net (code "32") (name "Net-(N9-PadB)") (class "Default")
      (node (ref "N9") (pin "B") (pinfunction "B_B") (pintype "passive"))
      (node (ref "R31") (pin "2") (pinfunction "2_2") (pintype "passive"))
      (node (ref "R48") (pin "1") (pinfunction "1_1") (pintype "passive"))
    )
    (net (code "33") (name "Net-(N9-PadC)") (class "Default")
      (node (ref "N9") (pin "C") (pinfunction "C_C") (pintype "passive"))
      (node (ref "V12") (pin "12") (pinfunction "CA_12") (pintype "passive"))
    )
    (net (code "34") (name "Net-(N10-PadB)") (class "Default")
      (node (ref "N10") (pin "B") (pinfunction "B_B") (pintype "passive"))
      (node (ref "R30") (pin "2") (pinfunction "2_2") (pintype "passive"))
      (node (ref "R51") (pin "1") (pinfunction "1_1") (pintype "passive"))
    )
    (net (code "35") (name "Net-(N10-PadC)") (class "Default")
      (node (ref "N10") (pin "C") (pinfunction "C_C") (pintype "passive"))
      (node (ref "V12") (pin "9") (pinfunction "CA_9") (pintype "passive"))
    )
    (net (code "36") (name "Net-(N11-PadB)") (class "Default")
      (node (ref "N11") (pin "B") (pinfunction "B_B") (pintype "passive"))
      (node (ref "R29") (pin "2") (pinfunction "2_2") (pintype "passive"))
      (node (ref "R52") (pin "1") (pinfunction "1_1") (pintype "passive"))
    )
    (net (code "37") (name "Net-(N11-PadC)") (class "Default")
      (node (ref "N11") (pin "C") (pinfunction "C_C") (pintype "passive"))
      (node (ref "V12") (pin "8") (pinfunction "CA_8") (pintype "passive"))
    )
    (net (code "38") (name "Net-(P3-1S)") (class "Default")
      (node (ref "P3") (pin "WIPER") (pinfunction "1S_WIPER") (pintype "passive"))
      (node (ref "U1") (pin "13") (pinfunction "-IN_13") (pintype "input"))
    )
    (net (code "39") (name "Net-(P4-1E)") (class "Default")
      (node (ref "P4") (pin "RIGHT") (pinfunction "1E_RIGHT") (pintype "passive"))
      (node (ref "X4-A") (pin "TP") (pinfunction "TP_TP") (pintype "bidirectional"))
    )
    (net (code "40") (name "Net-(R6-Pad1)") (class "Default")
      (node (ref "R6") (pin "1") (pinfunction "1_1") (pintype "passive"))
      (node (ref "X5-S") (pin "TP") (pinfunction "TP_TP") (pintype "bidirectional"))
    )
    (net (code "41") (name "Net-(R12-Pad2)") (class "Default")
      (node (ref "R12") (pin "2") (pinfunction "2_2") (pintype "passive"))
      (node (ref "V1") (pin "A") (pinfunction "A_A") (pintype "passive"))
    )
    (net (code "42") (name "Net-(R14-Pad1)") (class "Default")
      (node (ref "R14") (pin "1") (pinfunction "1_1") (pintype "passive"))
      (node (ref "X5-E") (pin "TP") (pinfunction "TP_TP") (pintype "bidirectional"))
    )
    (net (code "43") (name "Net-(R39-Pad1)") (class "Default")
      (node (ref "R39") (pin "1") (pinfunction "1_1") (pintype "passive"))
      (node (ref "V3") (pin "A") (pinfunction "A_A") (pintype "passive"))
    )
    (net (code "44") (name "Net-(R41-Pad1)") (class "Default")
      (node (ref "R41") (pin "1") (pinfunction "1_1") (pintype "passive"))
      (node (ref "R43") (pin "2") (pinfunction "2_2") (pintype "passive"))
    )
    (net (code "45") (name "Net-(S2-P)") (class "Default")
      (node (ref "R21") (pin "1") (pinfunction "1_1") (pintype "passive"))
      (node (ref "R23") (pin "2") (pinfunction "2_2") (pintype "passive"))
      (node (ref "S2") (pin "3") (pinfunction "P_3") (pintype "passive"))
      (node (ref "S2") (pin "4") (pinfunction "P1_4") (pintype "passive"))
      (node (ref "U3") (pin "5") (pinfunction "+IN_5") (pintype "input"))
    )
    (net (code "46") (name "Net-(U1A-+IN)") (class "Default")
      (node (ref "U1") (pin "3") (pinfunction "+IN_3") (pintype "input"))
      (node (ref "X4-S") (pin "TP") (pinfunction "TP_TP") (pintype "bidirectional"))
    )
    (net (code "47") (name "Net-(U1A-OUT)") (class "Default")
      (node (ref "R8") (pin "2") (pinfunction "2_2") (pintype "passive"))
      (node (ref "U1") (pin "1") (pinfunction "OUT_1") (pintype "output"))
      (node (ref "V4") (pin "C") (pinfunction "C_C") (pintype "passive"))
    )
    (net (code "48") (name "Net-(U1B-+IN)") (class "Default")
      (node (ref "R10") (pin "1") (pinfunction "1_1") (pintype "passive"))
      (node (ref "R11") (pin "2") (pinfunction "2_2") (pintype "passive"))
      (node (ref "U1") (pin "5") (pinfunction "+IN_5") (pintype "input"))
    )
    (net (code "49") (name "Net-(U1B--IN)") (class "Default")
      (node (ref "R8") (pin "1") (pinfunction "1_1") (pintype "passive"))
      (node (ref "U1") (pin "6") (pinfunction "-IN_6") (pintype "input"))
    )
    (net (code "50") (name "Net-(U1B-OUT)") (class "Default")
      (node (ref "R12") (pin "1") (pinfunction "1_1") (pintype "passive"))
      (node (ref "U1") (pin "7") (pinfunction "OUT_7") (pintype "output"))
    )
    (net (code "51") (name "Net-(U1C-+IN)") (class "Default")
      (node (ref "R3") (pin "2") (pinfunction "2_2") (pintype "passive"))
      (node (ref "R5") (pin "2") (pinfunction "2_2") (pintype "passive"))
      (node (ref "U1") (pin "10") (pinfunction "+IN_10") (pintype "input"))
    )
    (net (code "52") (name "Net-(U1C--IN)") (class "Default")
      (node (ref "R4") (pin "2") (pinfunction "2_2") (pintype "passive"))
      (node (ref "U1") (pin "9") (pinfunction "-IN_9") (pintype "input"))
      (node (ref "V2") (pin "A") (pinfunction "A_A") (pintype "passive"))
    )
    (net (code "53") (name "Net-(U1C-OUT)") (class "Default")
      (node (ref "R5") (pin "1") (pinfunction "1_1") (pintype "passive"))
      (node (ref "U1") (pin "8") (pinfunction "OUT_8") (pintype "output"))
      (node (ref "V2") (pin "C") (pinfunction "C_C") (pintype "passive"))
      (node (ref "X5-A") (pin "TP") (pinfunction "TP_TP") (pintype "bidirectional"))
    )
    (net (code "54") (name "Net-(U1D-+IN)") (class "Default")
      (node (ref "R6") (pin "2") (pinfunction "2_2") (pintype "passive"))
      (node (ref "U1") (pin "12") (pinfunction "+IN_12") (pintype "input"))
    )
    (net (code "55") (name "Net-(U1D-OUT)") (class "Default")
      (node (ref "R7") (pin "2") (pinfunction "2_2") (pintype "passive"))
      (node (ref "U1") (pin "14") (pinfunction "OUT_14") (pintype "output"))
    )
    (net (code "56") (name "Net-(U2-COMP)") (class "Default")
      (node (ref "C13") (pin "2") (pinfunction "2_2") (pintype "passive"))
      (node (ref "C14") (pin "1") (pinfunction "1_1") (pintype "passive"))
      (node (ref "U2") (pin "4") (pinfunction "COMP_4") (pintype "passive"))
    )
    (net (code "57") (name "Net-(U2-FB)") (class "Default")
      (node (ref "R13") (pin "1") (pinfunction "1_1") (pintype "passive"))
      (node (ref "R44") (pin "2") (pinfunction "2_2") (pintype "passive"))
      (node (ref "U2") (pin "5") (pinfunction "FB_5") (pintype "input"))
    )
    (net (code "58") (name "Net-(U2-OUT)") (class "Default")
      (node (ref "L2") (pin "1") (pinfunction "1_1") (pintype "passive"))
      (node (ref "U2") (pin "1") (pinfunction "OUT_1") (pintype "output"))
      (node (ref "V5") (pin "C") (pinfunction "C_C") (pintype "passive"))
    )
    (net (code "59") (name "Net-(U3A-+IN)") (class "Default")
      (node (ref "R19") (pin "2") (pinfunction "2_2") (pintype "passive"))
      (node (ref "R20") (pin "2") (pinfunction "2_2") (pintype "passive"))
      (node (ref "U3") (pin "3") (pinfunction "+IN_3") (pintype "input"))
    )
    (net (code "60") (name "Net-(U3A--IN)") (class "Default")
      (node (ref "R18") (pin "2") (pinfunction "2_2") (pintype "passive"))
      (node (ref "R46") (pin "1") (pinfunction "1_1") (pintype "passive"))
      (node (ref "U3") (pin "2") (pinfunction "-IN_2") (pintype "input"))
    )
    (net (code "61") (name "Net-(U3A-OUT)") (class "Default")
      (node (ref "R46") (pin "2") (pinfunction "2_2") (pintype "passive"))
      (node (ref "U3") (pin "1") (pinfunction "OUT_1") (pintype "output"))
      (node (ref "U3") (pin "6") (pinfunction "-IN_6") (pintype "input"))
    )
    (net (code "62") (name "Net-(U3B-OUT)") (class "Default")
      (node (ref "R2") (pin "2") (pinfunction "2_2") (pintype "passive"))
      (node (ref "R24") (pin "1") (pinfunction "1_1") (pintype "passive"))
      (node (ref "U3") (pin "7") (pinfunction "OUT_7") (pintype "output"))
    )
    (net (code "63") (name "Net-(U4A-+IN)") (class "Default")
      (node (ref "R9") (pin "2") (pinfunction "2_2") (pintype "passive"))
      (node (ref "U4") (pin "3") (pinfunction "+IN_3") (pintype "input"))
    )
    (net (code "64") (name "Net-(U4A--IN)") (class "Default")
      (node (ref "R49") (pin "2") (pinfunction "2_2") (pintype "passive"))
      (node (ref "R50") (pin "1") (pinfunction "1_1") (pintype "passive"))
      (node (ref "U4") (pin "2") (pinfunction "-IN_2") (pintype "input"))
    )
    (net (code "65") (name "Net-(U5-PB0(ICP))") (class "Default")
      (node (ref "R25") (pin "2") (pinfunction "2_2") (pintype "passive"))
      (node (ref "U5") (pin "12") (pinfunction "PB0(ICP)_12") (pintype "bidirectional"))
    )
    (net (code "66") (name "Net-(U5-PB1(OC1A))") (class "Default")
      (node (ref "R32") (pin "2") (pinfunction "2_2") (pintype "passive"))
      (node (ref "U5") (pin "13") (pinfunction "PB1(OC1A)_13") (pintype "bidirectional"))
    )
    (net (code "67") (name "Net-(U5-PB2(SS{slash}OC1B))") (class "Default")
      (node (ref "R33") (pin "2") (pinfunction "2_2") (pintype "passive"))
      (node (ref "U5") (pin "14") (pinfunction "PB2(SS/OC1B)_14") (pintype "bidirectional"))
    )
    (net (code "68") (name "Net-(U5-PB6(XTAL1{slash}TOSC1))") (class "Default")
      (node (ref "R37") (pin "2") (pinfunction "2_2") (pintype "passive"))
      (node (ref "U5") (pin "7") (pinfunction "PB6(XTAL1/TOSC1)_7") (pintype "bidirectional"))
    )
    (net (code "69") (name "Net-(U5-PB7(XTAL2{slash}TOSC2))") (class "Default")
      (node (ref "R38") (pin "2") (pinfunction "2_2") (pintype "passive"))
      (node (ref "U5") (pin "8") (pinfunction "PB7(XTAL2/TOSC2)_8") (pintype "bidirectional"))
    )
    (net (code "70") (name "ON_OFF") (class "Default")
      (node (ref "N1") (pin "1") (pinfunction "B_1") (pintype "passive"))
      (node (ref "R7") (pin "1") (pinfunction "1_1") (pintype "passive"))
      (node (ref "V10") (pin "A") (pinfunction "A_A") (pintype "passive"))
      (node (ref "V4") (pin "A") (pinfunction "A_A") (pintype "passive"))
      (node (ref "V9") (pin "A") (pinfunction "A_A") (pintype "passive"))
    )
    (net (code "71") (name "ON_OFF_T") (class "Default")
      (node (ref "R15") (pin "2") (pinfunction "2_2") (pintype "passive"))
      (node (ref "U5") (pin "2") (pinfunction "PD4(XCK/T0)_2") (pintype "bidirectional"))
    )
    (net (code "72") (name "ON{slash}OFF") (class "Default")
      (node (ref "R26") (pin "1") (pinfunction "1_1") (pintype "passive"))
      (node (ref "S1") (pin "3") (pinfunction "P_3") (pintype "passive"))
      (node (ref "S1") (pin "4") (pinfunction "P1_4") (pintype "passive"))
      (node (ref "U5") (pin "32") (pinfunction "PD2(INT0)_32") (pintype "bidirectional"))
    )
    (net (code "73") (name "PC0") (class "Default")
      (node (ref "R28") (pin "1") (pinfunction "1_1") (pintype "passive"))
      (node (ref "U5") (pin "23") (pinfunction "PC0(ADC0)_23") (pintype "bidirectional"))
    )
    (net (code "74") (name "PC1") (class "Default")
      (node (ref "R27") (pin "1") (pinfunction "1_1") (pintype "passive"))
      (node (ref "U5") (pin "24") (pinfunction "PC1(ADC1)_24") (pintype "bidirectional"))
    )
    (net (code "75") (name "PC2") (class "Default")
      (node (ref "R16") (pin "1") (pinfunction "1_1") (pintype "passive"))
      (node (ref "U5") (pin "25") (pinfunction "PC2(ADC2)_25") (pintype "bidirectional"))
    )
    (net (code "76") (name "PC3") (class "Default")
      (node (ref "R29") (pin "1") (pinfunction "1_1") (pintype "passive"))
      (node (ref "U5") (pin "26") (pinfunction "PC3(ADC3)_26") (pintype "bidirectional"))
    )
    (net (code "77") (name "PC4") (class "Default")
      (node (ref "R30") (pin "1") (pinfunction "1_1") (pintype "passive"))
      (node (ref "U5") (pin "27") (pinfunction "PC4(ADC4/SDA)_27") (pintype "bidirectional"))
    )
    (net (code "78") (name "PC5") (class "Default")
      (node (ref "R31") (pin "1") (pinfunction "1_1") (pintype "passive"))
      (node (ref "U5") (pin "28") (pinfunction "PC5(ADC5/SCL)_28") (pintype "bidirectional"))
    )
    (net (code "79") (name "RESET") (class "Default")
      (node (ref "R17") (pin "2") (pinfunction "2_2") (pintype "passive"))
      (node (ref "TP1") (pin "TP") (pinfunction "TP_TP") (pintype "bidirectional"))
      (node (ref "U5") (pin "29") (pinfunction "PC6(/RESET)_29") (pintype "bidirectional"))
    )
    (net (code "80") (name "SCK") (class "Default")
      (node (ref "R36") (pin "2") (pinfunction "2_2") (pintype "passive"))
      (node (ref "TP2") (pin "TP") (pinfunction "TP_TP") (pintype "bidirectional"))
      (node (ref "U5") (pin "17") (pinfunction "PB5(SCK)_17") (pintype "bidirectional"))
    )
    (net (code "81") (name "SHT_DTCT") (class "Default")
      (node (ref "R2") (pin "1") (pinfunction "1_1") (pintype "passive"))
      (node (ref "U5") (pin "1") (pinfunction "PD3(INT1)_1") (pintype "bidirectional"))
      (node (ref "V8") (pin "C") (pinfunction "C_C") (pintype "passive"))
    )
    (net (code "82") (name "VDC_IN") (class "Default")
      (node (ref "C1") (pin "+") (pinfunction "+_+") (pintype "passive"))
      (node (ref "C10") (pin "1") (pinfunction "1_1") (pintype "passive"))
      (node (ref "C11") (pin "1") (pinfunction "1_1") (pintype "passive"))
      (node (ref "C3") (pin "+") (pinfunction "+_+") (pintype "passive"))
      (node (ref "C4") (pin "1") (pinfunction "1_1") (pintype "passive"))
      (node (ref "C5") (pin "+") (pinfunction "+_+") (pintype "passive"))
      (node (ref "C6") (pin "+") (pinfunction "+_+") (pintype "passive"))
      (node (ref "C9") (pin "1") (pinfunction "1_1") (pintype "passive"))
      (node (ref "N1") (pin "2") (pinfunction "C_2") (pintype "passive"))
      (node (ref "N1") (pin "4") (pinfunction "C_4") (pintype "passive"))
      (node (ref "N2") (pin "C") (pinfunction "C_C") (pintype "passive"))
      (node (ref "R10") (pin "2") (pinfunction "2_2") (pintype "passive"))
      (node (ref "R21") (pin "2") (pinfunction "2_2") (pintype "passive"))
      (node (ref "R39") (pin "2") (pinfunction "2_2") (pintype "passive"))
      (node (ref "U1") (pin "4") (pinfunction "V+_4") (pintype "power_in"))
      (node (ref "U2") (pin "8") (pinfunction "VCC_8") (pintype "input"))
      (node (ref "U3") (pin "8") (pinfunction "V+_8") (pintype "power_in"))
      (node (ref "U4") (pin "8") (pinfunction "V+_8") (pintype "power_in"))
      (node (ref "V13") (pin "C") (pinfunction "C_C") (pintype "passive"))
      (node (ref "V6") (pin "C") (pinfunction "C_C") (pintype "passive"))
      (node (ref "X4") (pin "-1") (pinfunction "-1_-1") (pintype "passive"))
    )
    (net (code "83") (name "X6-OPAMP") (class "Default")
      (node (ref "R50") (pin "2") (pinfunction "2_2") (pintype "passive"))
      (node (ref "U1") (pin "2") (pinfunction "-IN_2") (pintype "input"))
      (node (ref "U4") (pin "1") (pinfunction "OUT_1") (pintype "output"))
      (node (ref "U4") (pin "5") (pinfunction "+IN_5") (pintype "input"))
    )
    (net (code "84") (name "unconnected-(P4-1A-PadLEFT)") (class "Default")
      (node (ref "P4") (pin "LEFT") (pinfunction "1A_LEFT") (pintype "passive"))
    )
    (net (code "85") (name "unconnected-(Q1-D-Pad3)") (class "Default")
      (node (ref "Q1") (pin "3") (pinfunction "D_3") (pintype "passive"))
    )
    (net (code "86") (name "unconnected-(Q1-G-Pad1)") (class "Default")
      (node (ref "Q1") (pin "1") (pinfunction "G_1") (pintype "passive"))
    )
    (net (code "87") (name "unconnected-(Q1-S-Pad2)") (class "Default")
      (node (ref "Q1") (pin "2") (pinfunction "S_2") (pintype "passive"))
    )
    (net (code "88") (name "unconnected-(U2-SYNC-Pad2)") (class "Default")
      (node (ref "U2") (pin "2") (pinfunction "SYNC_2") (pintype "bidirectional"))
    )
    (net (code "89") (name "unconnected-(U2-VREF-Pad6)") (class "Default")
      (node (ref "U2") (pin "6") (pinfunction "VREF_6") (pintype "output"))
    )
    (net (code "90") (name "unconnected-(U5-PD0(RXD)-Pad30)") (class "Default")
      (node (ref "U5") (pin "30") (pinfunction "PD0(RXD)_30") (pintype "bidirectional"))
    )
    (net (code "91") (name "unconnected-(U5-PD1(TXD)-Pad31)") (class "Default")
      (node (ref "U5") (pin "31") (pinfunction "PD1(TXD)_31") (pintype "bidirectional"))
    )
    (net (code "92") (name "unconnected-(U5-PD5(T1)-Pad9)") (class "Default")
      (node (ref "U5") (pin "9") (pinfunction "PD5(T1)_9") (pintype "bidirectional"))
    )
    (net (code "93") (name "unconnected-(U5-PD6(AIN0)-Pad10)") (class "Default")
      (node (ref "U5") (pin "10") (pinfunction "PD6(AIN0)_10") (pintype "bidirectional"))
    )
    (net (code "94") (name "unconnected-(U5-PD7(AIN1)-Pad11)") (class "Default")
      (node (ref "U5") (pin "11") (pinfunction "PD7(AIN1)_11") (pintype "bidirectional"))
    )
    (net (code "95") (name "unconnected-(X4-Pad-2)") (class "Default")
      (node (ref "X4") (pin "-2") (pinfunction "-2_-2") (pintype "passive"))
    )
  )
)
